# BMS_main.net
KiCad netlist of a schematic drawn in Altium Designer
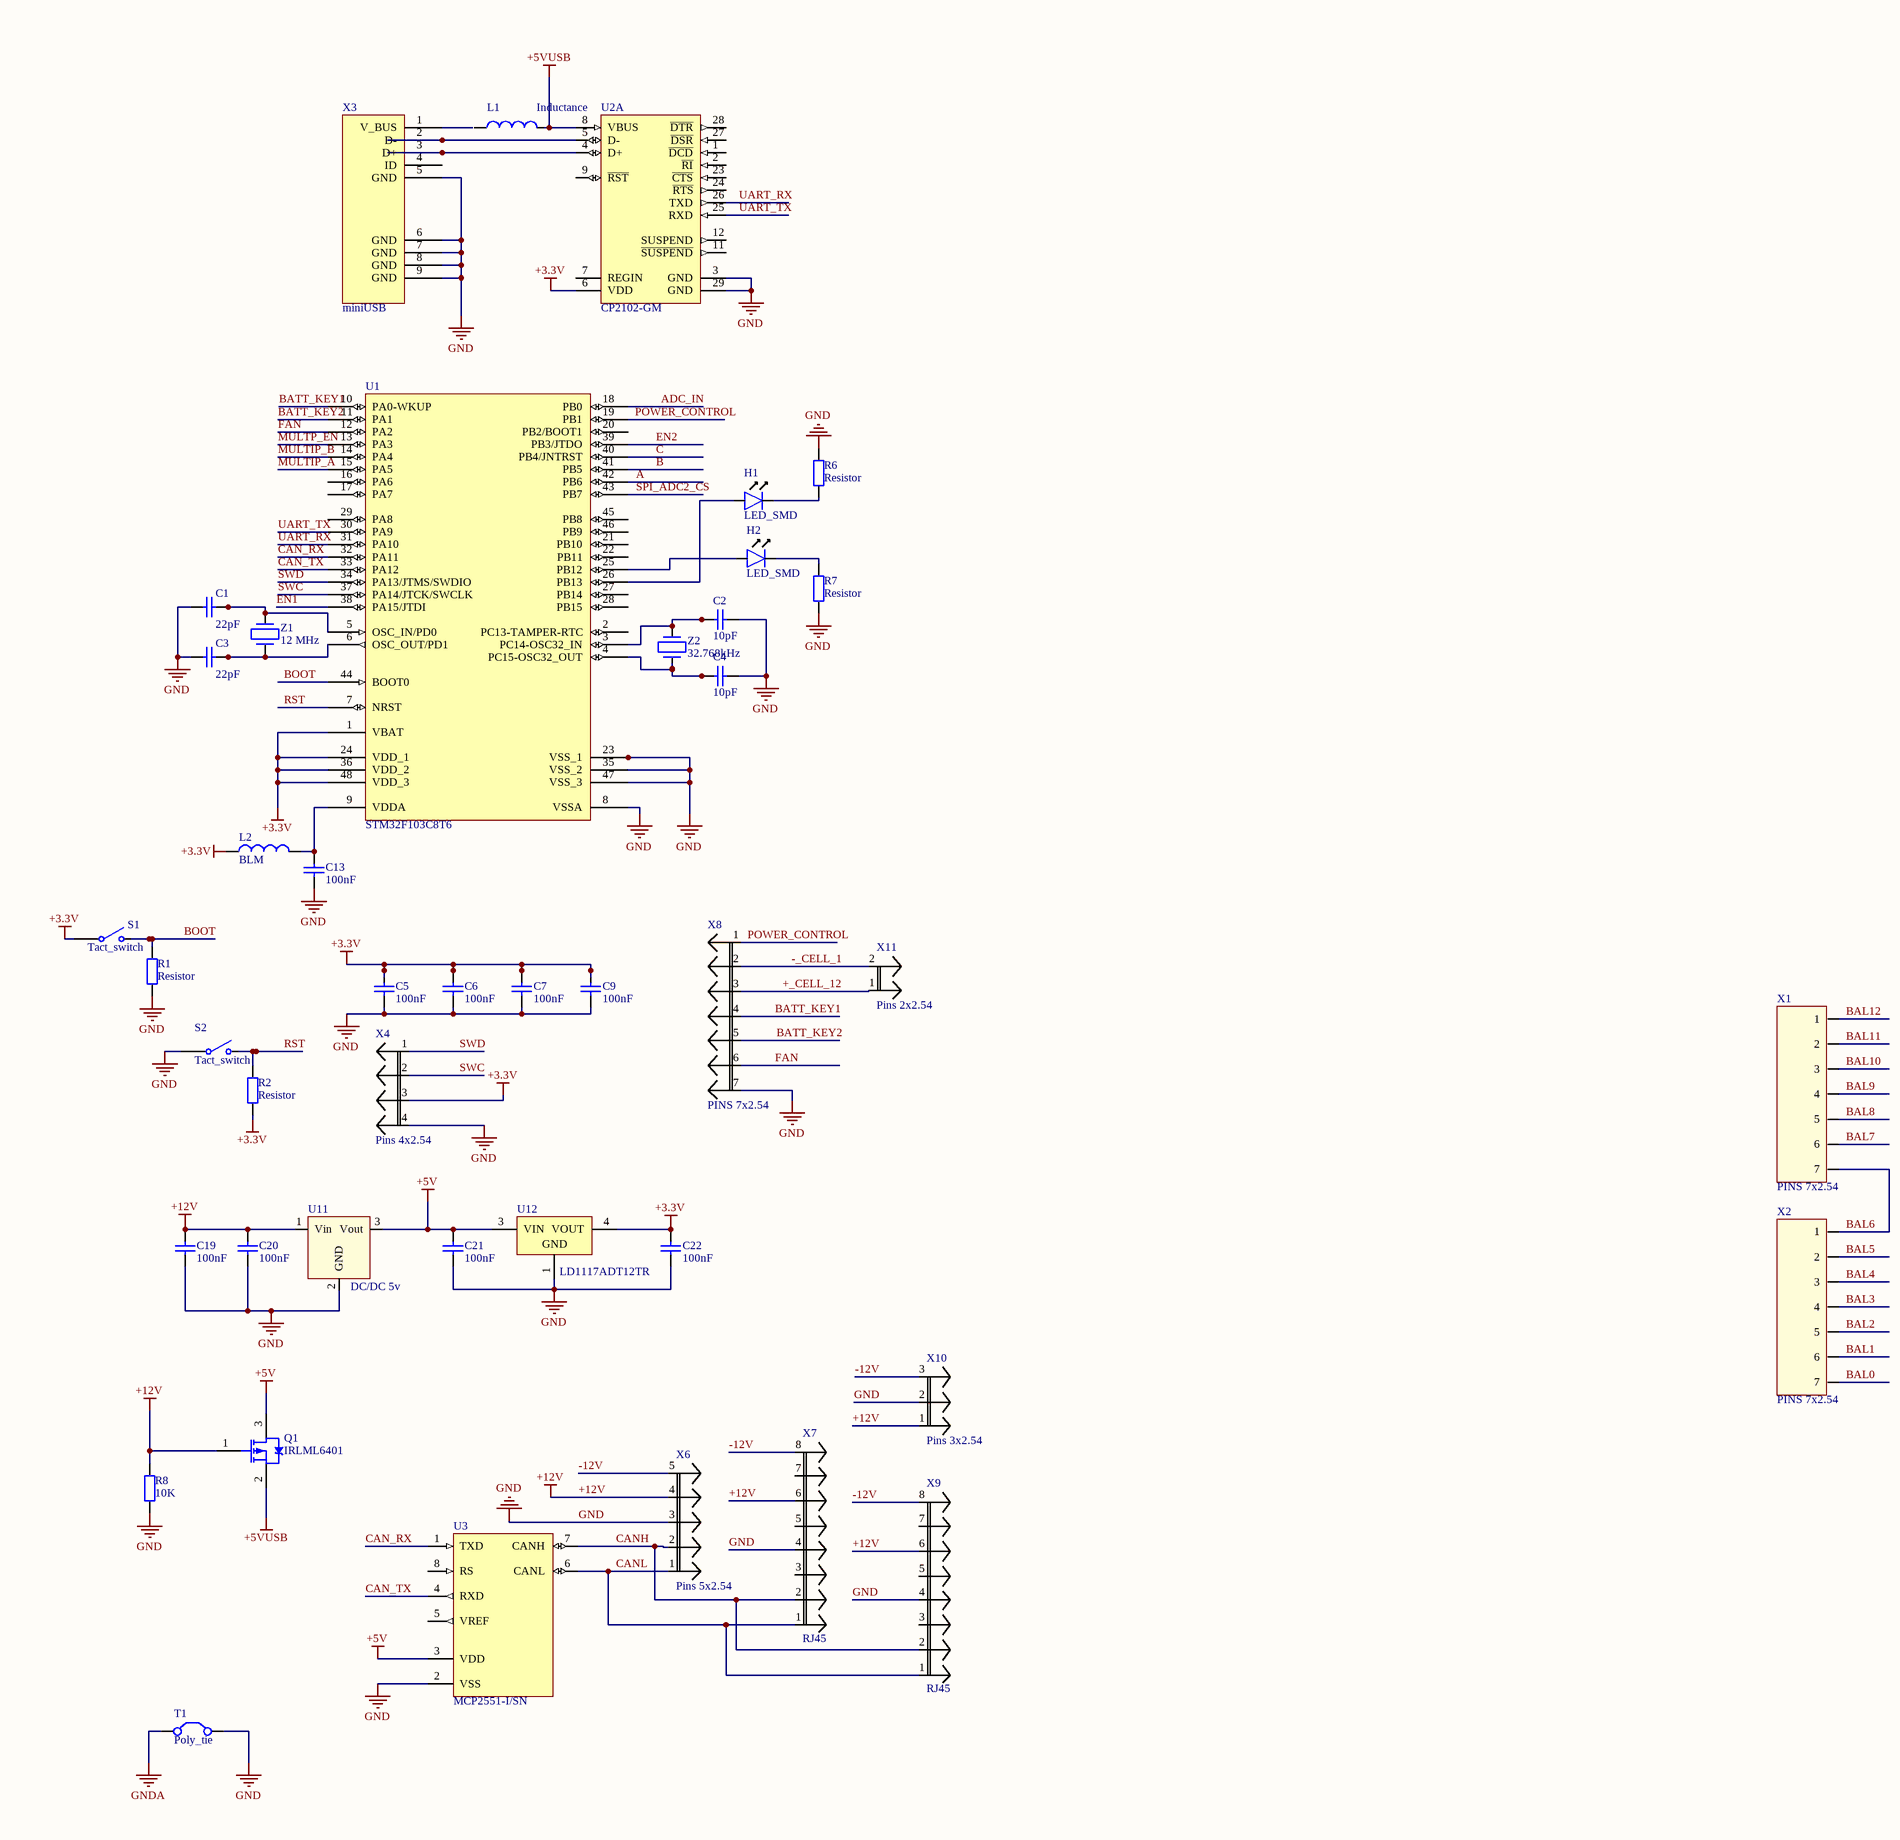
[diagram p0: BMS_main.SchDoc, left]
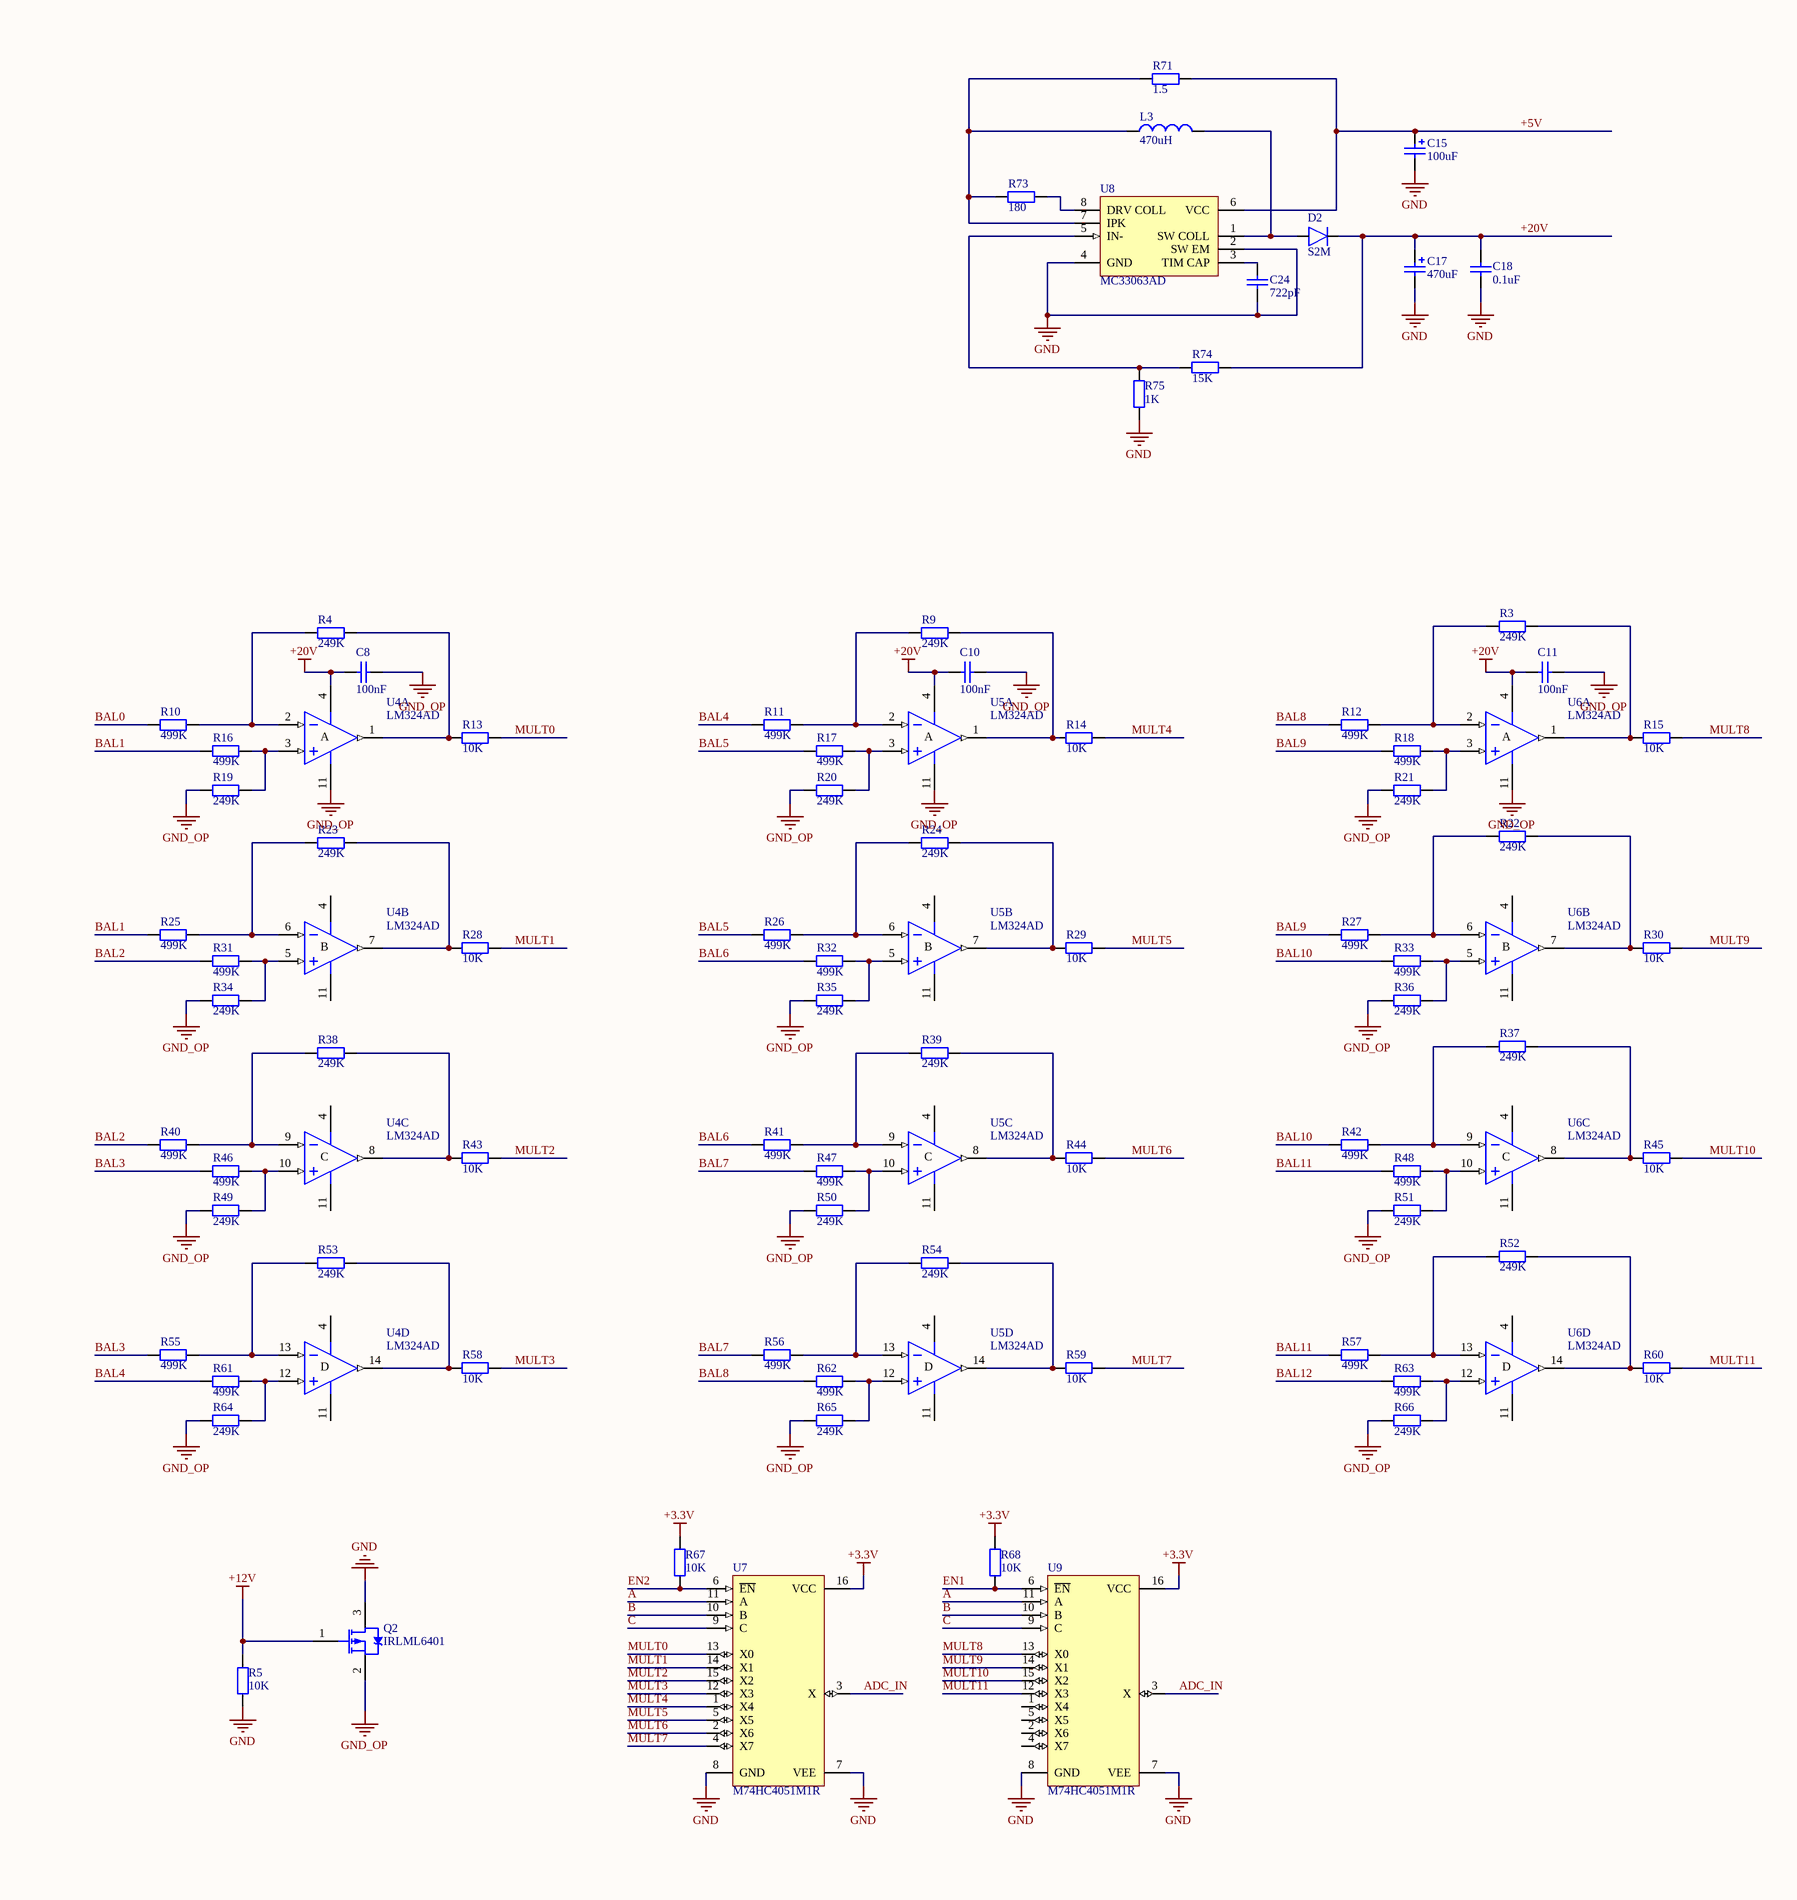
[diagram p1: BMS_main.SchDoc, right]

(export (version "E")
  (design (tool "Eeschema 10.0.6"))
  (components
    (comp (ref "C1") (value "22pF") (footprint "C0805") (libsource (lib "A_H_sch_lib") (part "Condensator")))
    (comp (ref "C2") (value "10pF") (footprint "C0805") (libsource (lib "A_H_sch_lib") (part "Condensator")))
    (comp (ref "C3") (value "22pF") (footprint "C0805") (libsource (lib "A_H_sch_lib") (part "Condensator")))
    (comp (ref "C4") (value "10pF") (footprint "C0805") (libsource (lib "A_H_sch_lib") (part "Condensator")))
    (comp (ref "C5") (value "100nF") (footprint "C0805") (libsource (lib "A_H_sch_lib") (part "Condensator")))
    (comp (ref "C6") (value "100nF") (footprint "C0805") (libsource (lib "A_H_sch_lib") (part "Condensator")))
    (comp (ref "C7") (value "100nF") (footprint "C0805") (libsource (lib "A_H_sch_lib") (part "Condensator")))
    (comp (ref "C8")
      (value "100nF")
      (footprint "A_H_pcb_lib:C0805")
      (libsource (lib "A_H_sch_lib") (part "Condensator"))
    )
    (comp (ref "C9") (value "100nF") (footprint "C0805") (libsource (lib "A_H_sch_lib") (part "Condensator")))
    (comp (ref "C10")
      (value "100nF")
      (footprint "A_H_pcb_lib:C0805")
      (libsource (lib "A_H_sch_lib") (part "Condensator"))
    )
    (comp (ref "C11")
      (value "100nF")
      (footprint "A_H_pcb_lib:C0805")
      (libsource (lib "A_H_sch_lib") (part "Condensator"))
    )
    (comp (ref "C13")
      (value "100nF")
      (footprint "C0805")
      (libsource (lib "A_H_sch_lib") (part "Condensator"))
    )
    (comp (ref "C15")
      (value "100uF")
      (footprint "A_H_pcb_lib:CAP_EL_SMD_6.3mm")
      (libsource (lib "A_H_sch_lib") (part "Cond_polar"))
    )
    (comp (ref "C17")
      (value "470uF")
      (footprint "A_H_pcb_lib:Cap_El_SMD_10mm")
      (libsource (lib "A_H_sch_lib") (part "Cond_polar"))
    )
    (comp (ref "C18")
      (value "0.1uF")
      (footprint "A_H_pcb_lib:C0805")
      (libsource (lib "A_H_sch_lib") (part "Condensator"))
    )
    (comp (ref "C19")
      (value "100nF")
      (footprint "C0805")
      (libsource (lib "A_H_sch_lib") (part "Condensator"))
    )
    (comp (ref "C20")
      (value "100nF")
      (footprint "C0805")
      (libsource (lib "A_H_sch_lib") (part "Condensator"))
    )
    (comp (ref "C21")
      (value "100nF")
      (footprint "C0805")
      (libsource (lib "A_H_sch_lib") (part "Condensator"))
    )
    (comp (ref "C22")
      (value "100nF")
      (footprint "C0805")
      (libsource (lib "A_H_sch_lib") (part "Condensator"))
    )
    (comp (ref "C24")
      (value "722pF")
      (footprint "A_H_pcb_lib:C0805")
      (libsource (lib "A_H_sch_lib") (part "Condensator"))
    )
    (comp (ref "D2")
      (value "S2M")
      (footprint "A_H_pcb_lib:SMB_DIODE")
      (libsource (lib "A_H_sch_lib") (part "Diod"))
    )
    (comp (ref "H1") (value "LED_SMD") (footprint "C0805") (libsource (lib "A_H_sch_lib") (part "LED_SMD")))
    (comp (ref "H2") (value "LED_SMD") (footprint "C0805") (libsource (lib "A_H_sch_lib") (part "LED_SMD")))
    (comp (ref "L1")
      (value "Inductance")
      (footprint "L0805")
      (libsource (lib "A_H_sch_lib") (part "Inductance"))
    )
    (comp (ref "L2") (value "BLM") (footprint "L0805") (libsource (lib "A_H_sch_lib") (part "Inductance")))
    (comp (ref "L3")
      (value "470uH")
      (footprint "A_H_pcb_lib:L1812")
      (libsource (lib "A_H_sch_lib") (part "Inductance"))
    )
    (comp (ref "Q1")
      (value "IRLML6401")
      (footprint "sot-23")
      (libsource (lib "A_H_sch_lib") (part "IRLML6401"))
    )
    (comp (ref "Q2")
      (value "IRLML6401")
      (footprint "sot-23")
      (libsource (lib "A_H_sch_lib") (part "IRLML6401"))
    )
    (comp (ref "R1") (value "Resistor") (footprint "R0805") (libsource (lib "") (part "Resistor_1")))
    (comp (ref "R2") (value "Resistor") (footprint "R0805") (libsource (lib "") (part "Resistor_1")))
    (comp (ref "R3") (value "249K") (footprint "R0805") (libsource (lib "A_H_sch_lib") (part "Resistor")))
    (comp (ref "R4") (value "249K") (footprint "R0805") (libsource (lib "A_H_sch_lib") (part "Resistor")))
    (comp (ref "R5") (value "10K") (footprint "R0805") (libsource (lib "") (part "Resistor_1")))
    (comp (ref "R6") (value "Resistor") (footprint "R0805") (libsource (lib "") (part "Resistor_1")))
    (comp (ref "R7") (value "Resistor") (footprint "R0805") (libsource (lib "") (part "Resistor_1")))
    (comp (ref "R8") (value "10K") (footprint "R0805") (libsource (lib "") (part "Resistor_1")))
    (comp (ref "R9") (value "249K") (footprint "R0805") (libsource (lib "A_H_sch_lib") (part "Resistor")))
    (comp (ref "R10") (value "499K") (footprint "R0805") (libsource (lib "A_H_sch_lib") (part "Resistor")))
    (comp (ref "R11") (value "499K") (footprint "R0805") (libsource (lib "A_H_sch_lib") (part "Resistor")))
    (comp (ref "R12") (value "499K") (footprint "R0805") (libsource (lib "A_H_sch_lib") (part "Resistor")))
    (comp (ref "R13") (value "10K") (footprint "R0805") (libsource (lib "A_H_sch_lib") (part "Resistor")))
    (comp (ref "R14") (value "10K") (footprint "R0805") (libsource (lib "A_H_sch_lib") (part "Resistor")))
    (comp (ref "R15") (value "10K") (footprint "R0805") (libsource (lib "A_H_sch_lib") (part "Resistor")))
    (comp (ref "R16") (value "499K") (footprint "R0805") (libsource (lib "A_H_sch_lib") (part "Resistor")))
    (comp (ref "R17") (value "499K") (footprint "R0805") (libsource (lib "A_H_sch_lib") (part "Resistor")))
    (comp (ref "R18") (value "499K") (footprint "R0805") (libsource (lib "A_H_sch_lib") (part "Resistor")))
    (comp (ref "R19") (value "249K") (footprint "R0805") (libsource (lib "A_H_sch_lib") (part "Resistor")))
    (comp (ref "R20") (value "249K") (footprint "R0805") (libsource (lib "A_H_sch_lib") (part "Resistor")))
    (comp (ref "R21") (value "249K") (footprint "R0805") (libsource (lib "A_H_sch_lib") (part "Resistor")))
    (comp (ref "R22") (value "249K") (footprint "R0805") (libsource (lib "A_H_sch_lib") (part "Resistor")))
    (comp (ref "R23") (value "249K") (footprint "R0805") (libsource (lib "A_H_sch_lib") (part "Resistor")))
    (comp (ref "R24") (value "249K") (footprint "R0805") (libsource (lib "A_H_sch_lib") (part "Resistor")))
    (comp (ref "R25") (value "499K") (footprint "R0805") (libsource (lib "A_H_sch_lib") (part "Resistor")))
    (comp (ref "R26") (value "499K") (footprint "R0805") (libsource (lib "A_H_sch_lib") (part "Resistor")))
    (comp (ref "R27") (value "499K") (footprint "R0805") (libsource (lib "A_H_sch_lib") (part "Resistor")))
    (comp (ref "R28") (value "10K") (footprint "R0805") (libsource (lib "A_H_sch_lib") (part "Resistor")))
    (comp (ref "R29") (value "10K") (footprint "R0805") (libsource (lib "A_H_sch_lib") (part "Resistor")))
    (comp (ref "R30") (value "10K") (footprint "R0805") (libsource (lib "A_H_sch_lib") (part "Resistor")))
    (comp (ref "R31") (value "499K") (footprint "R0805") (libsource (lib "A_H_sch_lib") (part "Resistor")))
    (comp (ref "R32") (value "499K") (footprint "R0805") (libsource (lib "A_H_sch_lib") (part "Resistor")))
    (comp (ref "R33") (value "499K") (footprint "R0805") (libsource (lib "A_H_sch_lib") (part "Resistor")))
    (comp (ref "R34") (value "249K") (footprint "R0805") (libsource (lib "A_H_sch_lib") (part "Resistor")))
    (comp (ref "R35") (value "249K") (footprint "R0805") (libsource (lib "A_H_sch_lib") (part "Resistor")))
    (comp (ref "R36") (value "249K") (footprint "R0805") (libsource (lib "A_H_sch_lib") (part "Resistor")))
    (comp (ref "R37") (value "249K") (footprint "R0805") (libsource (lib "A_H_sch_lib") (part "Resistor")))
    (comp (ref "R38") (value "249K") (footprint "R0805") (libsource (lib "A_H_sch_lib") (part "Resistor")))
    (comp (ref "R39") (value "249K") (footprint "R0805") (libsource (lib "A_H_sch_lib") (part "Resistor")))
    (comp (ref "R40") (value "499K") (footprint "R0805") (libsource (lib "A_H_sch_lib") (part "Resistor")))
    (comp (ref "R41") (value "499K") (footprint "R0805") (libsource (lib "A_H_sch_lib") (part "Resistor")))
    (comp (ref "R42") (value "499K") (footprint "R0805") (libsource (lib "A_H_sch_lib") (part "Resistor")))
    (comp (ref "R43") (value "10K") (footprint "R0805") (libsource (lib "A_H_sch_lib") (part "Resistor")))
    (comp (ref "R44") (value "10K") (footprint "R0805") (libsource (lib "A_H_sch_lib") (part "Resistor")))
    (comp (ref "R45") (value "10K") (footprint "R0805") (libsource (lib "A_H_sch_lib") (part "Resistor")))
    (comp (ref "R46") (value "499K") (footprint "R0805") (libsource (lib "A_H_sch_lib") (part "Resistor")))
    (comp (ref "R47") (value "499K") (footprint "R0805") (libsource (lib "A_H_sch_lib") (part "Resistor")))
    (comp (ref "R48") (value "499K") (footprint "R0805") (libsource (lib "A_H_sch_lib") (part "Resistor")))
    (comp (ref "R49") (value "249K") (footprint "R0805") (libsource (lib "A_H_sch_lib") (part "Resistor")))
    (comp (ref "R50") (value "249K") (footprint "R0805") (libsource (lib "A_H_sch_lib") (part "Resistor")))
    (comp (ref "R51") (value "249K") (footprint "R0805") (libsource (lib "A_H_sch_lib") (part "Resistor")))
    (comp (ref "R52") (value "249K") (footprint "R0805") (libsource (lib "A_H_sch_lib") (part "Resistor")))
    (comp (ref "R53") (value "249K") (footprint "R0805") (libsource (lib "A_H_sch_lib") (part "Resistor")))
    (comp (ref "R54") (value "249K") (footprint "R0805") (libsource (lib "A_H_sch_lib") (part "Resistor")))
    (comp (ref "R55") (value "499K") (footprint "R0805") (libsource (lib "A_H_sch_lib") (part "Resistor")))
    (comp (ref "R56") (value "499K") (footprint "R0805") (libsource (lib "A_H_sch_lib") (part "Resistor")))
    (comp (ref "R57") (value "499K") (footprint "R0805") (libsource (lib "A_H_sch_lib") (part "Resistor")))
    (comp (ref "R58") (value "10K") (footprint "R0805") (libsource (lib "A_H_sch_lib") (part "Resistor")))
    (comp (ref "R59") (value "10K") (footprint "R0805") (libsource (lib "A_H_sch_lib") (part "Resistor")))
    (comp (ref "R60") (value "10K") (footprint "R0805") (libsource (lib "A_H_sch_lib") (part "Resistor")))
    (comp (ref "R61") (value "499K") (footprint "R0805") (libsource (lib "A_H_sch_lib") (part "Resistor")))
    (comp (ref "R62") (value "499K") (footprint "R0805") (libsource (lib "A_H_sch_lib") (part "Resistor")))
    (comp (ref "R63") (value "499K") (footprint "R0805") (libsource (lib "A_H_sch_lib") (part "Resistor")))
    (comp (ref "R64") (value "249K") (footprint "R0805") (libsource (lib "A_H_sch_lib") (part "Resistor")))
    (comp (ref "R65") (value "249K") (footprint "R0805") (libsource (lib "A_H_sch_lib") (part "Resistor")))
    (comp (ref "R66") (value "249K") (footprint "R0805") (libsource (lib "A_H_sch_lib") (part "Resistor")))
    (comp (ref "R67") (value "10K") (footprint "R0805") (libsource (lib "") (part "Resistor_1")))
    (comp (ref "R68") (value "10K") (footprint "R0805") (libsource (lib "") (part "Resistor_1")))
    (comp (ref "R71") (value "1.5") (footprint "R0805") (libsource (lib "") (part "Resistor_2")))
    (comp (ref "R73") (value "180") (footprint "R0805") (libsource (lib "") (part "Resistor_2")))
    (comp (ref "R74") (value "15K") (footprint "R0805") (libsource (lib "A_H_sch_lib") (part "Resistor")))
    (comp (ref "R75") (value "1K") (footprint "R0805") (libsource (lib "") (part "Resistor_1")))
    (comp (ref "S1")
      (value "Tact_switch")
      (footprint "Tact_switch_smd")
      (libsource (lib "A_H_sch_lib") (part "Tact_switch"))
    )
    (comp (ref "S2")
      (value "Tact_switch")
      (footprint "Tact_switch_smd")
      (libsource (lib "A_H_sch_lib") (part "Tact_switch"))
    )
    (comp (ref "T1")
      (value "Poly_tie")
      (footprint "A_H_pcb_lib:Poly_tie_5x5")
      (libsource (lib "A_H_sch_lib") (part "Poly_tie"))
    )
    (comp (ref "U1")
      (value "STM32F103C8T6")
      (footprint "LQFP48_N")
      (description "STM32 ARM-based 32-bit MCU with 64 Kbytes Flash, 48-pin LQFP, Industrial Temperature")
      (fields (field (name "PUBLISHER") "Altium Limited"))
      (libsource (lib "ST Microcontroller 32-Bit STM32") (part "STM32F103C8T6"))
    )
    (comp (ref "U2")
      (value "CP2102-GM")
      (footprint "SLAB-QFN-28-3125x3125TP_N")
      (description "Single-Chip USB to UART Bridge, 1024 Bytes EEPROM, -40 to 85 degC, 28-pin QFN, Tube")
      (fields (field (name "MANUFACTURER") "Silicon Labs"))
      (libsource (lib "Silicon Labs Interface") (part "CP2102-GM"))
    )
    (comp (ref "U3")
      (value "MCP2551-I/SN")
      (footprint "SOIC-SN8_N")
      (description "High-Speed CAN Transceiver, 8-Pin SOIC, Industrial Temperature")
      (fields (field (name "PUBLISHER") "Altium Limited"))
      (libsource (lib "Microchip Interface") (part "MCP2551-I/SN"))
    )
    (comp (ref "U4")
      (value "LM324AD")
      (footprint "SO14_N")
      (description "Low-Power Quad Operational Amplifier")
      (fields (field (name "PUBLISHER") "Altium Limited"))
      (libsource (lib "ST Operational Amplifier") (part "LM324AD"))
    )
    (comp (ref "U5")
      (value "LM324AD")
      (footprint "SO14_N")
      (description "Low-Power Quad Operational Amplifier")
      (fields (field (name "PUBLISHER") "Altium Limited"))
      (libsource (lib "ST Operational Amplifier") (part "LM324AD"))
    )
    (comp (ref "U6")
      (value "LM324AD")
      (footprint "SO14_N")
      (description "Low-Power Quad Operational Amplifier")
      (fields (field (name "PUBLISHER") "Altium Limited"))
      (libsource (lib "ST Operational Amplifier") (part "LM324AD"))
    )
    (comp (ref "U7")
      (value "M74HC4051M1R")
      (footprint "SO16_N")
      (description "Analog Multiplexer/Demultiplexer Single 8-Channel")
      (fields (field (name "PUBLISHER") "Altium Limited"))
      (libsource (lib "ST Logic Multiplexer") (part "M74HC4051M1R"))
    )
    (comp (ref "U8")
      (value "MC33063AD")
      (footprint "751-05_N")
      (description "DC-to-DC Converter Control Circuit")
      (fields (field (name "PUBLISHER") "Altium Limited"))
      (libsource (lib "ON Semi Power Mgt DC-DC Converter") (part "MC33063AD"))
    )
    (comp (ref "U9")
      (value "M74HC4051M1R")
      (footprint "SO16_N")
      (description "Analog Multiplexer/Demultiplexer Single 8-Channel")
      (fields (field (name "PUBLISHER") "Altium Limited"))
      (libsource (lib "ST Logic Multiplexer") (part "M74HC4051M1R"))
    )
    (comp (ref "U11")
      (value "DC/DC 5v")
      (footprint "A_H_pcb_lib:DC/DC R-78E")
      (libsource (lib "A_H_sch_lib") (part "DC/DC R-78E"))
    )
    (comp (ref "U12")
      (value "LD1117ADT12TR")
      (footprint "TO-252_N")
      (description "1A, Low Drop Positive Voltage Regulator, 1.2V, 3-Pin DPAK, Tape and Reel")
      (libsource (lib "STMicroelectronics Power Management Linear Regulator") (part "LD1117ADT12TR"))
    )
    (comp (ref "X1")
      (value "PINS 7x2.54")
      (footprint "PINS 7X2.54")
      (libsource (lib "A_H_sch_lib") (part "PINS 7x2.54"))
    )
    (comp (ref "X2")
      (value "PINS 7x2.54")
      (footprint "PINS 7X2.54")
      (libsource (lib "A_H_sch_lib") (part "PINS 7x2.54"))
    )
    (comp (ref "X3")
      (value "miniUSB")
      (footprint "A_H_pcb_lib:miniUSB")
      (libsource (lib "A_H_sch_lib") (part "miniUSB"))
    )
    (comp (ref "X4")
      (value "Pins 4x2.54")
      (footprint "Pins 4x2.54")
      (libsource (lib "A_H_sch_lib") (part "Pins 4x2.54"))
    )
    (comp (ref "X6")
      (value "Pins 5x2.54")
      (footprint "Pins 5x2.54")
      (libsource (lib "A_H_sch_lib") (part "Pins 5x2.54"))
    )
    (comp (ref "X7")
      (value "RJ45")
      (footprint "A_H_pcb_lib:RJ45")
      (libsource (lib "A_H_sch_lib") (part "RJ45"))
    )
    (comp (ref "X8")
      (value "PINS 7x2.54")
      (footprint "PINS 7X2.54")
      (libsource (lib "") (part "PINS 7x2.54_1"))
    )
    (comp (ref "X9")
      (value "RJ45")
      (footprint "A_H_pcb_lib:RJ45")
      (libsource (lib "A_H_sch_lib") (part "RJ45"))
    )
    (comp (ref "X10")
      (value "Pins 3x2.54")
      (footprint "Pins 3x2.54")
      (libsource (lib "A_H_sch_lib") (part "Pins 3x2.54"))
    )
    (comp (ref "X11")
      (value "Pins 2x2.54")
      (footprint "Pins 2x2.54")
      (libsource (lib "A_H_sch_lib") (part "Pins 2x2.54"))
    )
    (comp (ref "Z1")
      (value "12 MHz")
      (footprint "kx 13 12MHz")
      (libsource (lib "A_H_sch_lib") (part "KX 13 Geyer"))
    )
    (comp (ref "Z2")
      (value "32.768kHz")
      (footprint "Geyer KX - 327S 32.768kHz")
      (libsource (lib "A_H_sch_lib") (part "Crystal Oscillator"))
    )
  )
  (nets
    (net (code "1") (name "+3.3V") (class "Default")
      (node (ref "C22") (pin "2") (pinfunction "2_2") (pintype "passive"))
      (node (ref "C5") (pin "2") (pinfunction "2_2") (pintype "passive"))
      (node (ref "C6") (pin "2") (pinfunction "2_2") (pintype "passive"))
      (node (ref "C7") (pin "2") (pinfunction "2_2") (pintype "passive"))
      (node (ref "C9") (pin "2") (pinfunction "2_2") (pintype "passive"))
      (node (ref "L2") (pin "1") (pinfunction "1_1") (pintype "passive"))
      (node (ref "R2") (pin "1") (pinfunction "1_1") (pintype "passive"))
      (node (ref "R67") (pin "2") (pinfunction "2_2") (pintype "passive"))
      (node (ref "R68") (pin "2") (pinfunction "2_2") (pintype "passive"))
      (node (ref "S1") (pin "1") (pinfunction "COMMON_1") (pintype "passive"))
      (node (ref "U1") (pin "1") (pinfunction "VBAT_1") (pintype "power_in"))
      (node (ref "U1") (pin "24") (pinfunction "VDD_1_24") (pintype "power_in"))
      (node (ref "U1") (pin "36") (pinfunction "VDD_2_36") (pintype "power_in"))
      (node (ref "U1") (pin "48") (pinfunction "VDD_3_48") (pintype "power_in"))
      (node (ref "U12") (pin "4") (pinfunction "VOUT_4") (pintype "power_in"))
      (node (ref "U2") (pin "6") (pinfunction "VDD_6") (pintype "power_in"))
      (node (ref "U7") (pin "16") (pinfunction "VCC_16") (pintype "power_in"))
      (node (ref "U9") (pin "16") (pinfunction "VCC_16") (pintype "power_in"))
      (node (ref "X4") (pin "3") (pinfunction "3_3") (pintype "passive"))
    )
    (net (code "2") (name "+5V") (class "Default")
      (node (ref "C15") (pin "1") (pinfunction "1_1") (pintype "passive"))
      (node (ref "C21") (pin "2") (pinfunction "2_2") (pintype "passive"))
      (node (ref "Q1") (pin "3") (pinfunction "D_3") (pintype "passive"))
      (node (ref "R71") (pin "1") (pinfunction "1_1") (pintype "passive"))
      (node (ref "U11") (pin "3") (pinfunction "Vout_3") (pintype "passive"))
      (node (ref "U12") (pin "3") (pinfunction "VIN_3") (pintype "power_in"))
      (node (ref "U3") (pin "3") (pinfunction "VDD_3") (pintype "power_in"))
      (node (ref "U8") (pin "6") (pinfunction "VCC_6") (pintype "power_in"))
    )
    (net (code "3") (name "+5VUSB") (class "Default")
      (node (ref "L1") (pin "2") (pinfunction "2_2") (pintype "passive"))
      (node (ref "Q1") (pin "2") (pinfunction "S_2") (pintype "passive"))
      (node (ref "U2") (pin "8") (pinfunction "VBUS_8") (pintype "input"))
    )
    (net (code "4") (name "+12V") (class "Default")
      (node (ref "C19") (pin "2") (pinfunction "2_2") (pintype "passive"))
      (node (ref "C20") (pin "2") (pinfunction "2_2") (pintype "passive"))
      (node (ref "Q1") (pin "1") (pinfunction "G_1") (pintype "passive"))
      (node (ref "Q2") (pin "1") (pinfunction "G_1") (pintype "passive"))
      (node (ref "R5") (pin "2") (pinfunction "2_2") (pintype "passive"))
      (node (ref "R8") (pin "2") (pinfunction "2_2") (pintype "passive"))
      (node (ref "U11") (pin "1") (pinfunction "Vin_1") (pintype "passive"))
      (node (ref "X10") (pin "1") (pinfunction "1_1") (pintype "passive"))
      (node (ref "X6") (pin "4") (pinfunction "4_4") (pintype "passive"))
      (node (ref "X7") (pin "6") (pinfunction "6_6") (pintype "passive"))
      (node (ref "X9") (pin "6") (pinfunction "6_6") (pintype "passive"))
    )
    (net (code "5") (name "+20V") (class "Default")
      (node (ref "C10") (pin "1") (pinfunction "1_1") (pintype "passive"))
      (node (ref "C11") (pin "1") (pinfunction "1_1") (pintype "passive"))
      (node (ref "C17") (pin "1") (pinfunction "1_1") (pintype "passive"))
      (node (ref "C18") (pin "2") (pinfunction "2_2") (pintype "passive"))
      (node (ref "C8") (pin "1") (pinfunction "1_1") (pintype "passive"))
      (node (ref "D2") (pin "2") (pinfunction "2_2") (pintype "passive"))
      (node (ref "R74") (pin "2") (pinfunction "2_2") (pintype "passive"))
      (node (ref "U4") (pin "4") (pinfunction "V+_4") (pintype "power_in"))
      (node (ref "U5") (pin "4") (pinfunction "V+_4") (pintype "power_in"))
      (node (ref "U6") (pin "4") (pinfunction "V+_4") (pintype "power_in"))
    )
    (net (code "6") (name "/+_CELL_12") (class "Default")
      (node (ref "X11") (pin "1") (pinfunction "1_1") (pintype "passive"))
      (node (ref "X8") (pin "3") (pinfunction "3_3") (pintype "passive"))
    )
    (net (code "7") (name "/-12V") (class "Default")
      (node (ref "X10") (pin "3") (pinfunction "3_3") (pintype "passive"))
      (node (ref "X6") (pin "5") (pinfunction "5_5") (pintype "passive"))
      (node (ref "X7") (pin "8") (pinfunction "8_8") (pintype "passive"))
      (node (ref "X9") (pin "8") (pinfunction "8_8") (pintype "passive"))
    )
    (net (code "8") (name "/-_CELL_1") (class "Default")
      (node (ref "X11") (pin "2") (pinfunction "2_2") (pintype "passive"))
      (node (ref "X8") (pin "2") (pinfunction "2_2") (pintype "passive"))
    )
    (net (code "9") (name "/A") (class "Default")
      (node (ref "U1") (pin "42") (pinfunction "PB6_42") (pintype "bidirectional"))
      (node (ref "U7") (pin "11") (pinfunction "A_11") (pintype "input"))
      (node (ref "U9") (pin "11") (pinfunction "A_11") (pintype "input"))
    )
    (net (code "10") (name "/ADC_IN") (class "Default")
      (node (ref "U1") (pin "18") (pinfunction "PB0_18") (pintype "bidirectional"))
      (node (ref "U7") (pin "3") (pinfunction "X_3") (pintype "bidirectional"))
      (node (ref "U9") (pin "3") (pinfunction "X_3") (pintype "bidirectional"))
    )
    (net (code "11") (name "/B") (class "Default")
      (node (ref "U1") (pin "41") (pinfunction "PB5_41") (pintype "bidirectional"))
      (node (ref "U7") (pin "10") (pinfunction "B_10") (pintype "input"))
      (node (ref "U9") (pin "10") (pinfunction "B_10") (pintype "input"))
    )
    (net (code "12") (name "/BAL0") (class "Default")
      (node (ref "R10") (pin "1") (pinfunction "1_1") (pintype "passive"))
      (node (ref "X2") (pin "7") (pinfunction "7_7") (pintype "passive"))
    )
    (net (code "13") (name "/BAL1") (class "Default")
      (node (ref "R16") (pin "1") (pinfunction "1_1") (pintype "passive"))
      (node (ref "R25") (pin "1") (pinfunction "1_1") (pintype "passive"))
      (node (ref "X2") (pin "6") (pinfunction "6_6") (pintype "passive"))
    )
    (net (code "14") (name "/BAL2") (class "Default")
      (node (ref "R31") (pin "1") (pinfunction "1_1") (pintype "passive"))
      (node (ref "R40") (pin "1") (pinfunction "1_1") (pintype "passive"))
      (node (ref "X2") (pin "5") (pinfunction "5_5") (pintype "passive"))
    )
    (net (code "15") (name "/BAL3") (class "Default")
      (node (ref "R46") (pin "1") (pinfunction "1_1") (pintype "passive"))
      (node (ref "R55") (pin "1") (pinfunction "1_1") (pintype "passive"))
      (node (ref "X2") (pin "4") (pinfunction "4_4") (pintype "passive"))
    )
    (net (code "16") (name "/BAL4") (class "Default")
      (node (ref "R11") (pin "1") (pinfunction "1_1") (pintype "passive"))
      (node (ref "R61") (pin "1") (pinfunction "1_1") (pintype "passive"))
      (node (ref "X2") (pin "3") (pinfunction "3_3") (pintype "passive"))
    )
    (net (code "17") (name "/BAL5") (class "Default")
      (node (ref "R17") (pin "1") (pinfunction "1_1") (pintype "passive"))
      (node (ref "R26") (pin "1") (pinfunction "1_1") (pintype "passive"))
      (node (ref "X2") (pin "2") (pinfunction "2_2") (pintype "passive"))
    )
    (net (code "18") (name "/BAL6") (class "Default")
      (node (ref "R32") (pin "1") (pinfunction "1_1") (pintype "passive"))
      (node (ref "R41") (pin "1") (pinfunction "1_1") (pintype "passive"))
      (node (ref "X1") (pin "7") (pinfunction "7_7") (pintype "passive"))
      (node (ref "X2") (pin "1") (pinfunction "1_1") (pintype "passive"))
    )
    (net (code "19") (name "/BAL7") (class "Default")
      (node (ref "R47") (pin "1") (pinfunction "1_1") (pintype "passive"))
      (node (ref "R56") (pin "1") (pinfunction "1_1") (pintype "passive"))
      (node (ref "X1") (pin "6") (pinfunction "6_6") (pintype "passive"))
    )
    (net (code "20") (name "/BAL8") (class "Default")
      (node (ref "R12") (pin "1") (pinfunction "1_1") (pintype "passive"))
      (node (ref "R62") (pin "1") (pinfunction "1_1") (pintype "passive"))
      (node (ref "X1") (pin "5") (pinfunction "5_5") (pintype "passive"))
    )
    (net (code "21") (name "/BAL9") (class "Default")
      (node (ref "R18") (pin "1") (pinfunction "1_1") (pintype "passive"))
      (node (ref "R27") (pin "1") (pinfunction "1_1") (pintype "passive"))
      (node (ref "X1") (pin "4") (pinfunction "4_4") (pintype "passive"))
    )
    (net (code "22") (name "/BAL10") (class "Default")
      (node (ref "R33") (pin "1") (pinfunction "1_1") (pintype "passive"))
      (node (ref "R42") (pin "1") (pinfunction "1_1") (pintype "passive"))
      (node (ref "X1") (pin "3") (pinfunction "3_3") (pintype "passive"))
    )
    (net (code "23") (name "/BAL11") (class "Default")
      (node (ref "R48") (pin "1") (pinfunction "1_1") (pintype "passive"))
      (node (ref "R57") (pin "1") (pinfunction "1_1") (pintype "passive"))
      (node (ref "X1") (pin "2") (pinfunction "2_2") (pintype "passive"))
    )
    (net (code "24") (name "/BAL12") (class "Default")
      (node (ref "R63") (pin "1") (pinfunction "1_1") (pintype "passive"))
      (node (ref "X1") (pin "1") (pinfunction "1_1") (pintype "passive"))
    )
    (net (code "25") (name "/BATT_KEY1") (class "Default")
      (node (ref "U1") (pin "10") (pinfunction "PA0-WKUP_10") (pintype "bidirectional"))
      (node (ref "X8") (pin "4") (pinfunction "4_4") (pintype "passive"))
    )
    (net (code "26") (name "/BATT_KEY2") (class "Default")
      (node (ref "U1") (pin "11") (pinfunction "PA1_11") (pintype "bidirectional"))
      (node (ref "X8") (pin "5") (pinfunction "5_5") (pintype "passive"))
    )
    (net (code "27") (name "/BOOT") (class "Default")
      (node (ref "R1") (pin "2") (pinfunction "2_2") (pintype "passive"))
      (node (ref "S1") (pin "2") (pinfunction "NO_2") (pintype "passive"))
      (node (ref "U1") (pin "44") (pinfunction "BOOT0_44") (pintype "input"))
    )
    (net (code "28") (name "/C") (class "Default")
      (node (ref "U1") (pin "40") (pinfunction "PB4/JNTRST_40") (pintype "bidirectional"))
      (node (ref "U7") (pin "9") (pinfunction "C_9") (pintype "input"))
      (node (ref "U9") (pin "9") (pinfunction "C_9") (pintype "input"))
    )
    (net (code "29") (name "/CANH") (class "Default")
      (node (ref "U3") (pin "7") (pinfunction "CANH_7") (pintype "bidirectional"))
      (node (ref "X6") (pin "2") (pinfunction "2_2") (pintype "passive"))
      (node (ref "X7") (pin "2") (pinfunction "2_2") (pintype "passive"))
      (node (ref "X9") (pin "2") (pinfunction "2_2") (pintype "passive"))
    )
    (net (code "30") (name "/CANL") (class "Default")
      (node (ref "U3") (pin "6") (pinfunction "CANL_6") (pintype "bidirectional"))
      (node (ref "X6") (pin "1") (pinfunction "1_1") (pintype "passive"))
      (node (ref "X7") (pin "1") (pinfunction "1_1") (pintype "passive"))
      (node (ref "X9") (pin "1") (pinfunction "1_1") (pintype "passive"))
    )
    (net (code "31") (name "/CAN_RX") (class "Default")
      (node (ref "U1") (pin "32") (pinfunction "PA11_32") (pintype "bidirectional"))
      (node (ref "U3") (pin "1") (pinfunction "TXD_1") (pintype "input"))
    )
    (net (code "32") (name "/CAN_TX") (class "Default")
      (node (ref "U1") (pin "33") (pinfunction "PA12_33") (pintype "bidirectional"))
      (node (ref "U3") (pin "4") (pinfunction "RXD_4") (pintype "output"))
    )
    (net (code "33") (name "/EN1") (class "Default")
      (node (ref "R68") (pin "1") (pinfunction "1_1") (pintype "passive"))
      (node (ref "U1") (pin "38") (pinfunction "PA15/JTDI_38") (pintype "bidirectional"))
      (node (ref "U9") (pin "6") (pinfunction "~{EN}_6") (pintype "input"))
    )
    (net (code "34") (name "/EN2") (class "Default")
      (node (ref "R67") (pin "1") (pinfunction "1_1") (pintype "passive"))
      (node (ref "U1") (pin "39") (pinfunction "PB3/JTDO_39") (pintype "bidirectional"))
      (node (ref "U7") (pin "6") (pinfunction "~{EN}_6") (pintype "input"))
    )
    (net (code "35") (name "/FAN") (class "Default")
      (node (ref "U1") (pin "12") (pinfunction "PA2_12") (pintype "bidirectional"))
      (node (ref "X8") (pin "6") (pinfunction "6_6") (pintype "passive"))
    )
    (net (code "36") (name "/MULT0") (class "Default")
      (node (ref "R13") (pin "2") (pinfunction "2_2") (pintype "passive"))
      (node (ref "U7") (pin "13") (pinfunction "X0_13") (pintype "bidirectional"))
    )
    (net (code "37") (name "/MULT1") (class "Default")
      (node (ref "R28") (pin "2") (pinfunction "2_2") (pintype "passive"))
      (node (ref "U7") (pin "14") (pinfunction "X1_14") (pintype "bidirectional"))
    )
    (net (code "38") (name "/MULT2") (class "Default")
      (node (ref "R43") (pin "2") (pinfunction "2_2") (pintype "passive"))
      (node (ref "U7") (pin "15") (pinfunction "X2_15") (pintype "bidirectional"))
    )
    (net (code "39") (name "/MULT3") (class "Default")
      (node (ref "R58") (pin "2") (pinfunction "2_2") (pintype "passive"))
      (node (ref "U7") (pin "12") (pinfunction "X3_12") (pintype "bidirectional"))
    )
    (net (code "40") (name "/MULT4") (class "Default")
      (node (ref "R14") (pin "2") (pinfunction "2_2") (pintype "passive"))
      (node (ref "U7") (pin "1") (pinfunction "X4_1") (pintype "bidirectional"))
    )
    (net (code "41") (name "/MULT5") (class "Default")
      (node (ref "R29") (pin "2") (pinfunction "2_2") (pintype "passive"))
      (node (ref "U7") (pin "5") (pinfunction "X5_5") (pintype "bidirectional"))
    )
    (net (code "42") (name "/MULT6") (class "Default")
      (node (ref "R44") (pin "2") (pinfunction "2_2") (pintype "passive"))
      (node (ref "U7") (pin "2") (pinfunction "X6_2") (pintype "bidirectional"))
    )
    (net (code "43") (name "/MULT7") (class "Default")
      (node (ref "R59") (pin "2") (pinfunction "2_2") (pintype "passive"))
      (node (ref "U7") (pin "4") (pinfunction "X7_4") (pintype "bidirectional"))
    )
    (net (code "44") (name "/MULT8") (class "Default")
      (node (ref "R15") (pin "2") (pinfunction "2_2") (pintype "passive"))
      (node (ref "U9") (pin "13") (pinfunction "X0_13") (pintype "bidirectional"))
    )
    (net (code "45") (name "/MULT9") (class "Default")
      (node (ref "R30") (pin "2") (pinfunction "2_2") (pintype "passive"))
      (node (ref "U9") (pin "14") (pinfunction "X1_14") (pintype "bidirectional"))
    )
    (net (code "46") (name "/MULT10") (class "Default")
      (node (ref "R45") (pin "2") (pinfunction "2_2") (pintype "passive"))
      (node (ref "U9") (pin "15") (pinfunction "X2_15") (pintype "bidirectional"))
    )
    (net (code "47") (name "/MULT11") (class "Default")
      (node (ref "R60") (pin "2") (pinfunction "2_2") (pintype "passive"))
      (node (ref "U9") (pin "12") (pinfunction "X3_12") (pintype "bidirectional"))
    )
    (net (code "48") (name "/MULTIP_A") (class "Default")
      (node (ref "U1") (pin "15") (pinfunction "PA5_15") (pintype "bidirectional"))
    )
    (net (code "49") (name "/MULTIP_B") (class "Default")
      (node (ref "U1") (pin "14") (pinfunction "PA4_14") (pintype "bidirectional"))
    )
    (net (code "50") (name "/MULTP_EN") (class "Default")
      (node (ref "U1") (pin "13") (pinfunction "PA3_13") (pintype "bidirectional"))
    )
    (net (code "51") (name "/POWER_CONTROL") (class "Default")
      (node (ref "U1") (pin "19") (pinfunction "PB1_19") (pintype "bidirectional"))
      (node (ref "X8") (pin "1") (pinfunction "1_1") (pintype "passive"))
    )
    (net (code "52") (name "/RST") (class "Default")
      (node (ref "R2") (pin "2") (pinfunction "2_2") (pintype "passive"))
      (node (ref "S2") (pin "2") (pinfunction "NO_2") (pintype "passive"))
      (node (ref "U1") (pin "7") (pinfunction "NRST_7") (pintype "bidirectional"))
    )
    (net (code "53") (name "/SPI_ADC2_CS") (class "Default")
      (node (ref "U1") (pin "43") (pinfunction "PB7_43") (pintype "bidirectional"))
    )
    (net (code "54") (name "/SWC") (class "Default")
      (node (ref "U1") (pin "37") (pinfunction "PA14/JTCK/SWCLK_37") (pintype "bidirectional"))
      (node (ref "X4") (pin "2") (pinfunction "2_2") (pintype "passive"))
    )
    (net (code "55") (name "/SWD") (class "Default")
      (node (ref "U1") (pin "34") (pinfunction "PA13/JTMS/SWDIO_34") (pintype "bidirectional"))
      (node (ref "X4") (pin "1") (pinfunction "1_1") (pintype "passive"))
    )
    (net (code "56") (name "/UART_RX") (class "Default")
      (node (ref "U1") (pin "31") (pinfunction "PA10_31") (pintype "bidirectional"))
      (node (ref "U2") (pin "26") (pinfunction "TXD_26") (pintype "output"))
    )
    (net (code "57") (name "/UART_TX") (class "Default")
      (node (ref "U1") (pin "30") (pinfunction "PA9_30") (pintype "bidirectional"))
      (node (ref "U2") (pin "25") (pinfunction "RXD_25") (pintype "input"))
    )
    (net (code "58") (name "GND") (class "Default")
      (node (ref "C1") (pin "1") (pinfunction "1_1") (pintype "passive"))
      (node (ref "C13") (pin "1") (pinfunction "1_1") (pintype "passive"))
      (node (ref "C15") (pin "2") (pinfunction "2_2") (pintype "passive"))
      (node (ref "C17") (pin "2") (pinfunction "2_2") (pintype "passive"))
      (node (ref "C18") (pin "1") (pinfunction "1_1") (pintype "passive"))
      (node (ref "C19") (pin "1") (pinfunction "1_1") (pintype "passive"))
      (node (ref "C2") (pin "1") (pinfunction "1_1") (pintype "passive"))
      (node (ref "C20") (pin "1") (pinfunction "1_1") (pintype "passive"))
      (node (ref "C21") (pin "1") (pinfunction "1_1") (pintype "passive"))
      (node (ref "C22") (pin "1") (pinfunction "1_1") (pintype "passive"))
      (node (ref "C24") (pin "1") (pinfunction "1_1") (pintype "passive"))
      (node (ref "C3") (pin "1") (pinfunction "1_1") (pintype "passive"))
      (node (ref "C4") (pin "1") (pinfunction "1_1") (pintype "passive"))
      (node (ref "C5") (pin "1") (pinfunction "1_1") (pintype "passive"))
      (node (ref "C6") (pin "1") (pinfunction "1_1") (pintype "passive"))
      (node (ref "C7") (pin "1") (pinfunction "1_1") (pintype "passive"))
      (node (ref "C9") (pin "1") (pinfunction "1_1") (pintype "passive"))
      (node (ref "Q2") (pin "3") (pinfunction "D_3") (pintype "passive"))
      (node (ref "R1") (pin "1") (pinfunction "1_1") (pintype "passive"))
      (node (ref "R5") (pin "1") (pinfunction "1_1") (pintype "passive"))
      (node (ref "R6") (pin "2") (pinfunction "2_2") (pintype "passive"))
      (node (ref "R7") (pin "1") (pinfunction "1_1") (pintype "passive"))
      (node (ref "R75") (pin "1") (pinfunction "1_1") (pintype "passive"))
      (node (ref "R8") (pin "1") (pinfunction "1_1") (pintype "passive"))
      (node (ref "S2") (pin "1") (pinfunction "COMMON_1") (pintype "passive"))
      (node (ref "T1") (pin "2") (pinfunction "C2_2") (pintype "passive"))
      (node (ref "U1") (pin "23") (pinfunction "VSS_1_23") (pintype "power_in"))
      (node (ref "U1") (pin "35") (pinfunction "VSS_2_35") (pintype "power_in"))
      (node (ref "U1") (pin "47") (pinfunction "VSS_3_47") (pintype "power_in"))
      (node (ref "U1") (pin "8") (pinfunction "VSSA_8") (pintype "power_in"))
      (node (ref "U11") (pin "2") (pinfunction "GND_2") (pintype "passive"))
      (node (ref "U12") (pin "1") (pinfunction "GND_1") (pintype "power_in"))
      (node (ref "U2") (pin "29") (pinfunction "GND_29") (pintype "power_in"))
      (node (ref "U2") (pin "3") (pinfunction "GND_3") (pintype "power_in"))
      (node (ref "U3") (pin "2") (pinfunction "VSS_2") (pintype "power_in"))
      (node (ref "U7") (pin "7") (pinfunction "VEE_7") (pintype "power_in"))
      (node (ref "U7") (pin "8") (pinfunction "GND_8") (pintype "power_in"))
      (node (ref "U8") (pin "2") (pinfunction "SW_EM_2") (pintype "passive"))
      (node (ref "U8") (pin "4") (pinfunction "GND_4") (pintype "power_in"))
      (node (ref "U9") (pin "7") (pinfunction "VEE_7") (pintype "power_in"))
      (node (ref "U9") (pin "8") (pinfunction "GND_8") (pintype "power_in"))
      (node (ref "X10") (pin "2") (pinfunction "2_2") (pintype "passive"))
      (node (ref "X3") (pin "5") (pinfunction "GND_5") (pintype "passive"))
      (node (ref "X3") (pin "6") (pinfunction "GND_6") (pintype "passive"))
      (node (ref "X3") (pin "7") (pinfunction "GND_7") (pintype "passive"))
      (node (ref "X3") (pin "8") (pinfunction "GND_8") (pintype "passive"))
      (node (ref "X3") (pin "9") (pinfunction "GND_9") (pintype "passive"))
      (node (ref "X4") (pin "4") (pinfunction "4_4") (pintype "passive"))
      (node (ref "X6") (pin "3") (pinfunction "3_3") (pintype "passive"))
      (node (ref "X7") (pin "4") (pinfunction "4_4") (pintype "passive"))
      (node (ref "X8") (pin "7") (pinfunction "7_7") (pintype "passive"))
      (node (ref "X9") (pin "4") (pinfunction "4_4") (pintype "passive"))
    )
    (net (code "59") (name "GNDA") (class "Default")
      (node (ref "T1") (pin "1") (pinfunction "C1_1") (pintype "passive"))
    )
    (net (code "60") (name "GND_OP") (class "Default")
      (node (ref "C10") (pin "2") (pinfunction "2_2") (pintype "passive"))
      (node (ref "C11") (pin "2") (pinfunction "2_2") (pintype "passive"))
      (node (ref "C8") (pin "2") (pinfunction "2_2") (pintype "passive"))
      (node (ref "Q2") (pin "2") (pinfunction "S_2") (pintype "passive"))
      (node (ref "R19") (pin "1") (pinfunction "1_1") (pintype "passive"))
      (node (ref "R20") (pin "1") (pinfunction "1_1") (pintype "passive"))
      (node (ref "R21") (pin "1") (pinfunction "1_1") (pintype "passive"))
      (node (ref "R34") (pin "1") (pinfunction "1_1") (pintype "passive"))
      (node (ref "R35") (pin "1") (pinfunction "1_1") (pintype "passive"))
      (node (ref "R36") (pin "1") (pinfunction "1_1") (pintype "passive"))
      (node (ref "R49") (pin "1") (pinfunction "1_1") (pintype "passive"))
      (node (ref "R50") (pin "1") (pinfunction "1_1") (pintype "passive"))
      (node (ref "R51") (pin "1") (pinfunction "1_1") (pintype "passive"))
      (node (ref "R64") (pin "1") (pinfunction "1_1") (pintype "passive"))
      (node (ref "R65") (pin "1") (pinfunction "1_1") (pintype "passive"))
      (node (ref "R66") (pin "1") (pinfunction "1_1") (pintype "passive"))
      (node (ref "U4") (pin "11") (pinfunction "V-_11") (pintype "power_in"))
      (node (ref "U5") (pin "11") (pinfunction "V-_11") (pintype "power_in"))
      (node (ref "U6") (pin "11") (pinfunction "V-_11") (pintype "power_in"))
    )
    (net (code "61") (name "Net-(H1-Pad2)") (class "Default")
      (node (ref "H1") (pin "2") (pinfunction "2_2") (pintype "passive"))
      (node (ref "R6") (pin "1") (pinfunction "1_1") (pintype "passive"))
    )
    (net (code "62") (name "Net-(H2-Pad2)") (class "Default")
      (node (ref "H2") (pin "2") (pinfunction "2_2") (pintype "passive"))
      (node (ref "R7") (pin "2") (pinfunction "2_2") (pintype "passive"))
    )
    (net (code "63") (name "Net-(U1-OSC_IN{slash}PD0)") (class "Default")
      (node (ref "C1") (pin "2") (pinfunction "2_2") (pintype "passive"))
      (node (ref "U1") (pin "5") (pinfunction "OSC_IN/PD0_5") (pintype "input"))
      (node (ref "Z1") (pin "1") (pinfunction "1_1") (pintype "passive"))
    )
    (net (code "64") (name "Net-(U1-OSC_OUT{slash}PD1)") (class "Default")
      (node (ref "C3") (pin "2") (pinfunction "2_2") (pintype "passive"))
      (node (ref "U1") (pin "6") (pinfunction "OSC_OUT/PD1_6") (pintype "output"))
      (node (ref "Z1") (pin "3") (pinfunction "3_3") (pintype "passive"))
    )
    (net (code "65") (name "Net-(U1-PB12)") (class "Default")
      (node (ref "H2") (pin "1") (pinfunction "1_1") (pintype "passive"))
      (node (ref "U1") (pin "25") (pinfunction "PB12_25") (pintype "bidirectional"))
    )
    (net (code "66") (name "Net-(U1-PB13)") (class "Default")
      (node (ref "H1") (pin "1") (pinfunction "1_1") (pintype "passive"))
      (node (ref "U1") (pin "26") (pinfunction "PB13_26") (pintype "bidirectional"))
    )
    (net (code "67") (name "Net-(U1-PC14-OSC32_IN)") (class "Default")
      (node (ref "C2") (pin "2") (pinfunction "2_2") (pintype "passive"))
      (node (ref "U1") (pin "3") (pinfunction "PC14-OSC32_IN_3") (pintype "bidirectional"))
      (node (ref "Z2") (pin "1") (pinfunction "1_1") (pintype "passive"))
    )
    (net (code "68") (name "Net-(U1-PC15-OSC32_OUT)") (class "Default")
      (node (ref "C4") (pin "2") (pinfunction "2_2") (pintype "passive"))
      (node (ref "U1") (pin "4") (pinfunction "PC15-OSC32_OUT_4") (pintype "bidirectional"))
      (node (ref "Z2") (pin "2") (pinfunction "2_2") (pintype "passive"))
    )
    (net (code "69") (name "Net-(U1-VDDA)") (class "Default")
      (node (ref "C13") (pin "2") (pinfunction "2_2") (pintype "passive"))
      (node (ref "L2") (pin "2") (pinfunction "2_2") (pintype "passive"))
      (node (ref "U1") (pin "9") (pinfunction "VDDA_9") (pintype "power_in"))
    )
    (net (code "70") (name "Net-(U2A-D+)") (class "Default")
      (node (ref "U2") (pin "4") (pinfunction "D+_4") (pintype "bidirectional"))
      (node (ref "X3") (pin "3") (pinfunction "D+_3") (pintype "passive"))
    )
    (net (code "71") (name "Net-(U2A-D-)") (class "Default")
      (node (ref "U2") (pin "5") (pinfunction "D-_5") (pintype "bidirectional"))
      (node (ref "X3") (pin "2") (pinfunction "D-_2") (pintype "passive"))
    )
    (net (code "72") (name "Net-(U4A-IN+)") (class "Default")
      (node (ref "R16") (pin "2") (pinfunction "2_2") (pintype "passive"))
      (node (ref "R19") (pin "2") (pinfunction "2_2") (pintype "passive"))
      (node (ref "U4") (pin "3") (pinfunction "IN+_3") (pintype "input"))
    )
    (net (code "73") (name "Net-(U4A-IN-)") (class "Default")
      (node (ref "R10") (pin "2") (pinfunction "2_2") (pintype "passive"))
      (node (ref "R4") (pin "1") (pinfunction "1_1") (pintype "passive"))
      (node (ref "U4") (pin "2") (pinfunction "IN-_2") (pintype "input"))
    )
    (net (code "74") (name "Net-(U4A-OUT)") (class "Default")
      (node (ref "R13") (pin "1") (pinfunction "1_1") (pintype "passive"))
      (node (ref "R4") (pin "2") (pinfunction "2_2") (pintype "passive"))
      (node (ref "U4") (pin "1") (pinfunction "OUT_1") (pintype "output"))
    )
    (net (code "75") (name "Net-(U4B-IN+)") (class "Default")
      (node (ref "R31") (pin "2") (pinfunction "2_2") (pintype "passive"))
      (node (ref "R34") (pin "2") (pinfunction "2_2") (pintype "passive"))
      (node (ref "U4") (pin "5") (pinfunction "IN+_5") (pintype "input"))
    )
    (net (code "76") (name "Net-(U4B-IN-)") (class "Default")
      (node (ref "R23") (pin "1") (pinfunction "1_1") (pintype "passive"))
      (node (ref "R25") (pin "2") (pinfunction "2_2") (pintype "passive"))
      (node (ref "U4") (pin "6") (pinfunction "IN-_6") (pintype "input"))
    )
    (net (code "77") (name "Net-(U4B-OUT)") (class "Default")
      (node (ref "R23") (pin "2") (pinfunction "2_2") (pintype "passive"))
      (node (ref "R28") (pin "1") (pinfunction "1_1") (pintype "passive"))
      (node (ref "U4") (pin "7") (pinfunction "OUT_7") (pintype "output"))
    )
    (net (code "78") (name "Net-(U4C-IN+)") (class "Default")
      (node (ref "R46") (pin "2") (pinfunction "2_2") (pintype "passive"))
      (node (ref "R49") (pin "2") (pinfunction "2_2") (pintype "passive"))
      (node (ref "U4") (pin "10") (pinfunction "IN+_10") (pintype "input"))
    )
    (net (code "79") (name "Net-(U4C-IN-)") (class "Default")
      (node (ref "R38") (pin "1") (pinfunction "1_1") (pintype "passive"))
      (node (ref "R40") (pin "2") (pinfunction "2_2") (pintype "passive"))
      (node (ref "U4") (pin "9") (pinfunction "IN-_9") (pintype "input"))
    )
    (net (code "80") (name "Net-(U4C-OUT)") (class "Default")
      (node (ref "R38") (pin "2") (pinfunction "2_2") (pintype "passive"))
      (node (ref "R43") (pin "1") (pinfunction "1_1") (pintype "passive"))
      (node (ref "U4") (pin "8") (pinfunction "OUT_8") (pintype "output"))
    )
    (net (code "81") (name "Net-(U4D-IN+)") (class "Default")
      (node (ref "R61") (pin "2") (pinfunction "2_2") (pintype "passive"))
      (node (ref "R64") (pin "2") (pinfunction "2_2") (pintype "passive"))
      (node (ref "U4") (pin "12") (pinfunction "IN+_12") (pintype "input"))
    )
    (net (code "82") (name "Net-(U4D-IN-)") (class "Default")
      (node (ref "R53") (pin "1") (pinfunction "1_1") (pintype "passive"))
      (node (ref "R55") (pin "2") (pinfunction "2_2") (pintype "passive"))
      (node (ref "U4") (pin "13") (pinfunction "IN-_13") (pintype "input"))
    )
    (net (code "83") (name "Net-(U4D-OUT)") (class "Default")
      (node (ref "R53") (pin "2") (pinfunction "2_2") (pintype "passive"))
      (node (ref "R58") (pin "1") (pinfunction "1_1") (pintype "passive"))
      (node (ref "U4") (pin "14") (pinfunction "OUT_14") (pintype "output"))
    )
    (net (code "84") (name "Net-(U5A-IN+)") (class "Default")
      (node (ref "R17") (pin "2") (pinfunction "2_2") (pintype "passive"))
      (node (ref "R20") (pin "2") (pinfunction "2_2") (pintype "passive"))
      (node (ref "U5") (pin "3") (pinfunction "IN+_3") (pintype "input"))
    )
    (net (code "85") (name "Net-(U5A-IN-)") (class "Default")
      (node (ref "R11") (pin "2") (pinfunction "2_2") (pintype "passive"))
      (node (ref "R9") (pin "1") (pinfunction "1_1") (pintype "passive"))
      (node (ref "U5") (pin "2") (pinfunction "IN-_2") (pintype "input"))
    )
    (net (code "86") (name "Net-(U5A-OUT)") (class "Default")
      (node (ref "R14") (pin "1") (pinfunction "1_1") (pintype "passive"))
      (node (ref "R9") (pin "2") (pinfunction "2_2") (pintype "passive"))
      (node (ref "U5") (pin "1") (pinfunction "OUT_1") (pintype "output"))
    )
    (net (code "87") (name "Net-(U5B-IN+)") (class "Default")
      (node (ref "R32") (pin "2") (pinfunction "2_2") (pintype "passive"))
      (node (ref "R35") (pin "2") (pinfunction "2_2") (pintype "passive"))
      (node (ref "U5") (pin "5") (pinfunction "IN+_5") (pintype "input"))
    )
    (net (code "88") (name "Net-(U5B-IN-)") (class "Default")
      (node (ref "R24") (pin "1") (pinfunction "1_1") (pintype "passive"))
      (node (ref "R26") (pin "2") (pinfunction "2_2") (pintype "passive"))
      (node (ref "U5") (pin "6") (pinfunction "IN-_6") (pintype "input"))
    )
    (net (code "89") (name "Net-(U5B-OUT)") (class "Default")
      (node (ref "R24") (pin "2") (pinfunction "2_2") (pintype "passive"))
      (node (ref "R29") (pin "1") (pinfunction "1_1") (pintype "passive"))
      (node (ref "U5") (pin "7") (pinfunction "OUT_7") (pintype "output"))
    )
    (net (code "90") (name "Net-(U5C-IN+)") (class "Default")
      (node (ref "R47") (pin "2") (pinfunction "2_2") (pintype "passive"))
      (node (ref "R50") (pin "2") (pinfunction "2_2") (pintype "passive"))
      (node (ref "U5") (pin "10") (pinfunction "IN+_10") (pintype "input"))
    )
    (net (code "91") (name "Net-(U5C-IN-)") (class "Default")
      (node (ref "R39") (pin "1") (pinfunction "1_1") (pintype "passive"))
      (node (ref "R41") (pin "2") (pinfunction "2_2") (pintype "passive"))
      (node (ref "U5") (pin "9") (pinfunction "IN-_9") (pintype "input"))
    )
    (net (code "92") (name "Net-(U5C-OUT)") (class "Default")
      (node (ref "R39") (pin "2") (pinfunction "2_2") (pintype "passive"))
      (node (ref "R44") (pin "1") (pinfunction "1_1") (pintype "passive"))
      (node (ref "U5") (pin "8") (pinfunction "OUT_8") (pintype "output"))
    )
    (net (code "93") (name "Net-(U5D-IN+)") (class "Default")
      (node (ref "R62") (pin "2") (pinfunction "2_2") (pintype "passive"))
      (node (ref "R65") (pin "2") (pinfunction "2_2") (pintype "passive"))
      (node (ref "U5") (pin "12") (pinfunction "IN+_12") (pintype "input"))
    )
    (net (code "94") (name "Net-(U5D-IN-)") (class "Default")
      (node (ref "R54") (pin "1") (pinfunction "1_1") (pintype "passive"))
      (node (ref "R56") (pin "2") (pinfunction "2_2") (pintype "passive"))
      (node (ref "U5") (pin "13") (pinfunction "IN-_13") (pintype "input"))
    )
    (net (code "95") (name "Net-(U5D-OUT)") (class "Default")
      (node (ref "R54") (pin "2") (pinfunction "2_2") (pintype "passive"))
      (node (ref "R59") (pin "1") (pinfunction "1_1") (pintype "passive"))
      (node (ref "U5") (pin "14") (pinfunction "OUT_14") (pintype "output"))
    )
    (net (code "96") (name "Net-(U6A-IN+)") (class "Default")
      (node (ref "R18") (pin "2") (pinfunction "2_2") (pintype "passive"))
      (node (ref "R21") (pin "2") (pinfunction "2_2") (pintype "passive"))
      (node (ref "U6") (pin "3") (pinfunction "IN+_3") (pintype "input"))
    )
    (net (code "97") (name "Net-(U6A-IN-)") (class "Default")
      (node (ref "R12") (pin "2") (pinfunction "2_2") (pintype "passive"))
      (node (ref "R3") (pin "1") (pinfunction "1_1") (pintype "passive"))
      (node (ref "U6") (pin "2") (pinfunction "IN-_2") (pintype "input"))
    )
    (net (code "98") (name "Net-(U6A-OUT)") (class "Default")
      (node (ref "R15") (pin "1") (pinfunction "1_1") (pintype "passive"))
      (node (ref "R3") (pin "2") (pinfunction "2_2") (pintype "passive"))
      (node (ref "U6") (pin "1") (pinfunction "OUT_1") (pintype "output"))
    )
    (net (code "99") (name "Net-(U6B-IN+)") (class "Default")
      (node (ref "R33") (pin "2") (pinfunction "2_2") (pintype "passive"))
      (node (ref "R36") (pin "2") (pinfunction "2_2") (pintype "passive"))
      (node (ref "U6") (pin "5") (pinfunction "IN+_5") (pintype "input"))
    )
    (net (code "100") (name "Net-(U6B-IN-)") (class "Default")
      (node (ref "R22") (pin "1") (pinfunction "1_1") (pintype "passive"))
      (node (ref "R27") (pin "2") (pinfunction "2_2") (pintype "passive"))
      (node (ref "U6") (pin "6") (pinfunction "IN-_6") (pintype "input"))
    )
    (net (code "101") (name "Net-(U6B-OUT)") (class "Default")
      (node (ref "R22") (pin "2") (pinfunction "2_2") (pintype "passive"))
      (node (ref "R30") (pin "1") (pinfunction "1_1") (pintype "passive"))
      (node (ref "U6") (pin "7") (pinfunction "OUT_7") (pintype "output"))
    )
    (net (code "102") (name "Net-(U6C-IN+)") (class "Default")
      (node (ref "R48") (pin "2") (pinfunction "2_2") (pintype "passive"))
      (node (ref "R51") (pin "2") (pinfunction "2_2") (pintype "passive"))
      (node (ref "U6") (pin "10") (pinfunction "IN+_10") (pintype "input"))
    )
    (net (code "103") (name "Net-(U6C-IN-)") (class "Default")
      (node (ref "R37") (pin "1") (pinfunction "1_1") (pintype "passive"))
      (node (ref "R42") (pin "2") (pinfunction "2_2") (pintype "passive"))
      (node (ref "U6") (pin "9") (pinfunction "IN-_9") (pintype "input"))
    )
    (net (code "104") (name "Net-(U6C-OUT)") (class "Default")
      (node (ref "R37") (pin "2") (pinfunction "2_2") (pintype "passive"))
      (node (ref "R45") (pin "1") (pinfunction "1_1") (pintype "passive"))
      (node (ref "U6") (pin "8") (pinfunction "OUT_8") (pintype "output"))
    )
    (net (code "105") (name "Net-(U6D-IN+)") (class "Default")
      (node (ref "R63") (pin "2") (pinfunction "2_2") (pintype "passive"))
      (node (ref "R66") (pin "2") (pinfunction "2_2") (pintype "passive"))
      (node (ref "U6") (pin "12") (pinfunction "IN+_12") (pintype "input"))
    )
    (net (code "106") (name "Net-(U6D-IN-)") (class "Default")
      (node (ref "R52") (pin "1") (pinfunction "1_1") (pintype "passive"))
      (node (ref "R57") (pin "2") (pinfunction "2_2") (pintype "passive"))
      (node (ref "U6") (pin "13") (pinfunction "IN-_13") (pintype "input"))
    )
    (net (code "107") (name "Net-(U6D-OUT)") (class "Default")
      (node (ref "R52") (pin "2") (pinfunction "2_2") (pintype "passive"))
      (node (ref "R60") (pin "1") (pinfunction "1_1") (pintype "passive"))
      (node (ref "U6") (pin "14") (pinfunction "OUT_14") (pintype "output"))
    )
    (net (code "108") (name "Net-(U8-DRV_COLL)") (class "Default")
      (node (ref "R73") (pin "1") (pinfunction "1_1") (pintype "passive"))
      (node (ref "U8") (pin "8") (pinfunction "DRV_COLL_8") (pintype "open_collector"))
    )
    (net (code "109") (name "Net-(U8-IN-)") (class "Default")
      (node (ref "R74") (pin "1") (pinfunction "1_1") (pintype "passive"))
      (node (ref "R75") (pin "2") (pinfunction "2_2") (pintype "passive"))
      (node (ref "U8") (pin "5") (pinfunction "IN-_5") (pintype "input"))
    )
    (net (code "110") (name "Net-(U8-IPK)") (class "Default")
      (node (ref "L3") (pin "1") (pinfunction "1_1") (pintype "passive"))
      (node (ref "R71") (pin "2") (pinfunction "2_2") (pintype "passive"))
      (node (ref "R73") (pin "2") (pinfunction "2_2") (pintype "passive"))
      (node (ref "U8") (pin "7") (pinfunction "IPK_7") (pintype "passive"))
    )
    (net (code "111") (name "Net-(U8-SW_COLL)") (class "Default")
      (node (ref "D2") (pin "1") (pinfunction "1_1") (pintype "passive"))
      (node (ref "L3") (pin "2") (pinfunction "2_2") (pintype "passive"))
      (node (ref "U8") (pin "1") (pinfunction "SW_COLL_1") (pintype "passive"))
    )
    (net (code "112") (name "Net-(U8-TIM_CAP)") (class "Default")
      (node (ref "C24") (pin "2") (pinfunction "2_2") (pintype "passive"))
      (node (ref "U8") (pin "3") (pinfunction "TIM_CAP_3") (pintype "passive"))
    )
    (net (code "113") (name "unconnected-(L1-Pad1)") (class "Default")
      (node (ref "L1") (pin "1") (pinfunction "1_1") (pintype "passive"))
    )
    (net (code "114") (name "unconnected-(U1-PA6-Pad16)") (class "Default")
      (node (ref "U1") (pin "16") (pinfunction "PA6_16") (pintype "bidirectional"))
    )
    (net (code "115") (name "unconnected-(U1-PA7-Pad17)") (class "Default")
      (node (ref "U1") (pin "17") (pinfunction "PA7_17") (pintype "bidirectional"))
    )
    (net (code "116") (name "unconnected-(U1-PA8-Pad29)") (class "Default")
      (node (ref "U1") (pin "29") (pinfunction "PA8_29") (pintype "bidirectional"))
    )
    (net (code "117") (name "unconnected-(U1-PB2{slash}BOOT1-Pad20)") (class "Default")
      (node (ref "U1") (pin "20") (pinfunction "PB2/BOOT1_20") (pintype "bidirectional"))
    )
    (net (code "118") (name "unconnected-(U1-PB8-Pad45)") (class "Default")
      (node (ref "U1") (pin "45") (pinfunction "PB8_45") (pintype "bidirectional"))
    )
    (net (code "119") (name "unconnected-(U1-PB9-Pad46)") (class "Default")
      (node (ref "U1") (pin "46") (pinfunction "PB9_46") (pintype "bidirectional"))
    )
    (net (code "120") (name "unconnected-(U1-PB10-Pad21)") (class "Default")
      (node (ref "U1") (pin "21") (pinfunction "PB10_21") (pintype "bidirectional"))
    )
    (net (code "121") (name "unconnected-(U1-PB11-Pad22)") (class "Default")
      (node (ref "U1") (pin "22") (pinfunction "PB11_22") (pintype "bidirectional"))
    )
    (net (code "122") (name "unconnected-(U1-PB14-Pad27)") (class "Default")
      (node (ref "U1") (pin "27") (pinfunction "PB14_27") (pintype "bidirectional"))
    )
    (net (code "123") (name "unconnected-(U1-PB15-Pad28)") (class "Default")
      (node (ref "U1") (pin "28") (pinfunction "PB15_28") (pintype "bidirectional"))
    )
    (net (code "124") (name "unconnected-(U1-PC13-TAMPER-RTC-Pad2)") (class "Default")
      (node (ref "U1") (pin "2") (pinfunction "PC13-TAMPER-RTC_2") (pintype "bidirectional"))
    )
    (net (code "125") (name "unconnected-(U2A-REGIN-Pad7)") (class "Default")
      (node (ref "U2") (pin "7") (pinfunction "REGIN_7") (pintype "power_in"))
    )
    (net (code "126") (name "unconnected-(U2A-SUSPEND-Pad12)") (class "Default")
      (node (ref "U2") (pin "12") (pinfunction "SUSPEND_12") (pintype "output"))
    )
    (net (code "127") (name "unconnected-(U2A-~{CTS}-Pad23)") (class "Default")
      (node (ref "U2") (pin "23") (pinfunction "~{CTS}_23") (pintype "input"))
    )
    (net (code "128") (name "unconnected-(U2A-~{DCD}-Pad1)") (class "Default")
      (node (ref "U2") (pin "1") (pinfunction "~{DCD}_1") (pintype "input"))
    )
    (net (code "129") (name "unconnected-(U2A-~{DSR}-Pad27)") (class "Default")
      (node (ref "U2") (pin "27") (pinfunction "~{DSR}_27") (pintype "input"))
    )
    (net (code "130") (name "unconnected-(U2A-~{DTR}-Pad28)") (class "Default")
      (node (ref "U2") (pin "28") (pinfunction "~{DTR}_28") (pintype "output"))
    )
    (net (code "131") (name "unconnected-(U2A-~{RI}-Pad2)") (class "Default")
      (node (ref "U2") (pin "2") (pinfunction "~{RI}_2") (pintype "input"))
    )
    (net (code "132") (name "unconnected-(U2A-~{RST}-Pad9)") (class "Default")
      (node (ref "U2") (pin "9") (pinfunction "~{RST}_9") (pintype "bidirectional"))
    )
    (net (code "133") (name "unconnected-(U2A-~{RTS}-Pad24)") (class "Default")
      (node (ref "U2") (pin "24") (pinfunction "~{RTS}_24") (pintype "output"))
    )
    (net (code "134") (name "unconnected-(U2A-~{SUSPEND}-Pad11)") (class "Default")
      (node (ref "U2") (pin "11") (pinfunction "~{SUSPEND}_11") (pintype "output"))
    )
    (net (code "135") (name "unconnected-(U3-RS-Pad8)") (class "Default")
      (node (ref "U3") (pin "8") (pinfunction "RS_8") (pintype "input"))
    )
    (net (code "136") (name "unconnected-(U3-VREF-Pad5)") (class "Default")
      (node (ref "U3") (pin "5") (pinfunction "VREF_5") (pintype "output"))
    )
    (net (code "137") (name "unconnected-(U4B-V+-Pad4)") (class "Default")
      (node (ref "U4") (pin "4") (pinfunction "V+_4") (pintype "power_in"))
    )
    (net (code "138") (name "unconnected-(U4B-V--Pad11)") (class "Default")
      (node (ref "U4") (pin "11") (pinfunction "V-_11") (pintype "power_in"))
    )
    (net (code "139") (name "unconnected-(U4C-V+-Pad4)") (class "Default")
      (node (ref "U4") (pin "4") (pinfunction "V+_4") (pintype "power_in"))
    )
    (net (code "140") (name "unconnected-(U4C-V--Pad11)") (class "Default")
      (node (ref "U4") (pin "11") (pinfunction "V-_11") (pintype "power_in"))
    )
    (net (code "141") (name "unconnected-(U4D-V+-Pad4)") (class "Default")
      (node (ref "U4") (pin "4") (pinfunction "V+_4") (pintype "power_in"))
    )
    (net (code "142") (name "unconnected-(U4D-V--Pad11)") (class "Default")
      (node (ref "U4") (pin "11") (pinfunction "V-_11") (pintype "power_in"))
    )
    (net (code "143") (name "unconnected-(U5B-V+-Pad4)") (class "Default")
      (node (ref "U5") (pin "4") (pinfunction "V+_4") (pintype "power_in"))
    )
    (net (code "144") (name "unconnected-(U5B-V--Pad11)") (class "Default")
      (node (ref "U5") (pin "11") (pinfunction "V-_11") (pintype "power_in"))
    )
    (net (code "145") (name "unconnected-(U5C-V+-Pad4)") (class "Default")
      (node (ref "U5") (pin "4") (pinfunction "V+_4") (pintype "power_in"))
    )
    (net (code "146") (name "unconnected-(U5C-V--Pad11)") (class "Default")
      (node (ref "U5") (pin "11") (pinfunction "V-_11") (pintype "power_in"))
    )
    (net (code "147") (name "unconnected-(U5D-V+-Pad4)") (class "Default")
      (node (ref "U5") (pin "4") (pinfunction "V+_4") (pintype "power_in"))
    )
    (net (code "148") (name "unconnected-(U5D-V--Pad11)") (class "Default")
      (node (ref "U5") (pin "11") (pinfunction "V-_11") (pintype "power_in"))
    )
    (net (code "149") (name "unconnected-(U6B-V+-Pad4)") (class "Default")
      (node (ref "U6") (pin "4") (pinfunction "V+_4") (pintype "power_in"))
    )
    (net (code "150") (name "unconnected-(U6B-V--Pad11)") (class "Default")
      (node (ref "U6") (pin "11") (pinfunction "V-_11") (pintype "power_in"))
    )
    (net (code "151") (name "unconnected-(U6C-V+-Pad4)") (class "Default")
      (node (ref "U6") (pin "4") (pinfunction "V+_4") (pintype "power_in"))
    )
    (net (code "152") (name "unconnected-(U6C-V--Pad11)") (class "Default")
      (node (ref "U6") (pin "11") (pinfunction "V-_11") (pintype "power_in"))
    )
    (net (code "153") (name "unconnected-(U6D-V+-Pad4)") (class "Default")
      (node (ref "U6") (pin "4") (pinfunction "V+_4") (pintype "power_in"))
    )
    (net (code "154") (name "unconnected-(U6D-V--Pad11)") (class "Default")
      (node (ref "U6") (pin "11") (pinfunction "V-_11") (pintype "power_in"))
    )
    (net (code "155") (name "unconnected-(U9-X4-Pad1)") (class "Default")
      (node (ref "U9") (pin "1") (pinfunction "X4_1") (pintype "bidirectional"))
    )
    (net (code "156") (name "unconnected-(U9-X5-Pad5)") (class "Default")
      (node (ref "U9") (pin "5") (pinfunction "X5_5") (pintype "bidirectional"))
    )
    (net (code "157") (name "unconnected-(U9-X6-Pad2)") (class "Default")
      (node (ref "U9") (pin "2") (pinfunction "X6_2") (pintype "bidirectional"))
    )
    (net (code "158") (name "unconnected-(U9-X7-Pad4)") (class "Default")
      (node (ref "U9") (pin "4") (pinfunction "X7_4") (pintype "bidirectional"))
    )
    (net (code "159") (name "unconnected-(X3-ID-Pad4)") (class "Default")
      (node (ref "X3") (pin "4") (pinfunction "ID_4") (pintype "passive"))
    )
    (net (code "160") (name "unconnected-(X3-V_BUS-Pad1)") (class "Default")
      (node (ref "X3") (pin "1") (pinfunction "V_BUS_1") (pintype "passive"))
    )
    (net (code "161") (name "unconnected-(X7-Pad3)") (class "Default")
      (node (ref "X7") (pin "3") (pinfunction "3_3") (pintype "passive"))
    )
    (net (code "162") (name "unconnected-(X7-Pad5)") (class "Default")
      (node (ref "X7") (pin "5") (pinfunction "5_5") (pintype "passive"))
    )
    (net (code "163") (name "unconnected-(X7-Pad7)") (class "Default")
      (node (ref "X7") (pin "7") (pinfunction "7_7") (pintype "passive"))
    )
    (net (code "164") (name "unconnected-(X9-Pad3)") (class "Default")
      (node (ref "X9") (pin "3") (pinfunction "3_3") (pintype "passive"))
    )
    (net (code "165") (name "unconnected-(X9-Pad5)") (class "Default")
      (node (ref "X9") (pin "5") (pinfunction "5_5") (pintype "passive"))
    )
    (net (code "166") (name "unconnected-(X9-Pad7)") (class "Default")
      (node (ref "X9") (pin "7") (pinfunction "7_7") (pintype "passive"))
    )
  )
)
